# ImageSensor_IMX415.net
KiCad netlist of a schematic drawn in Altium Designer
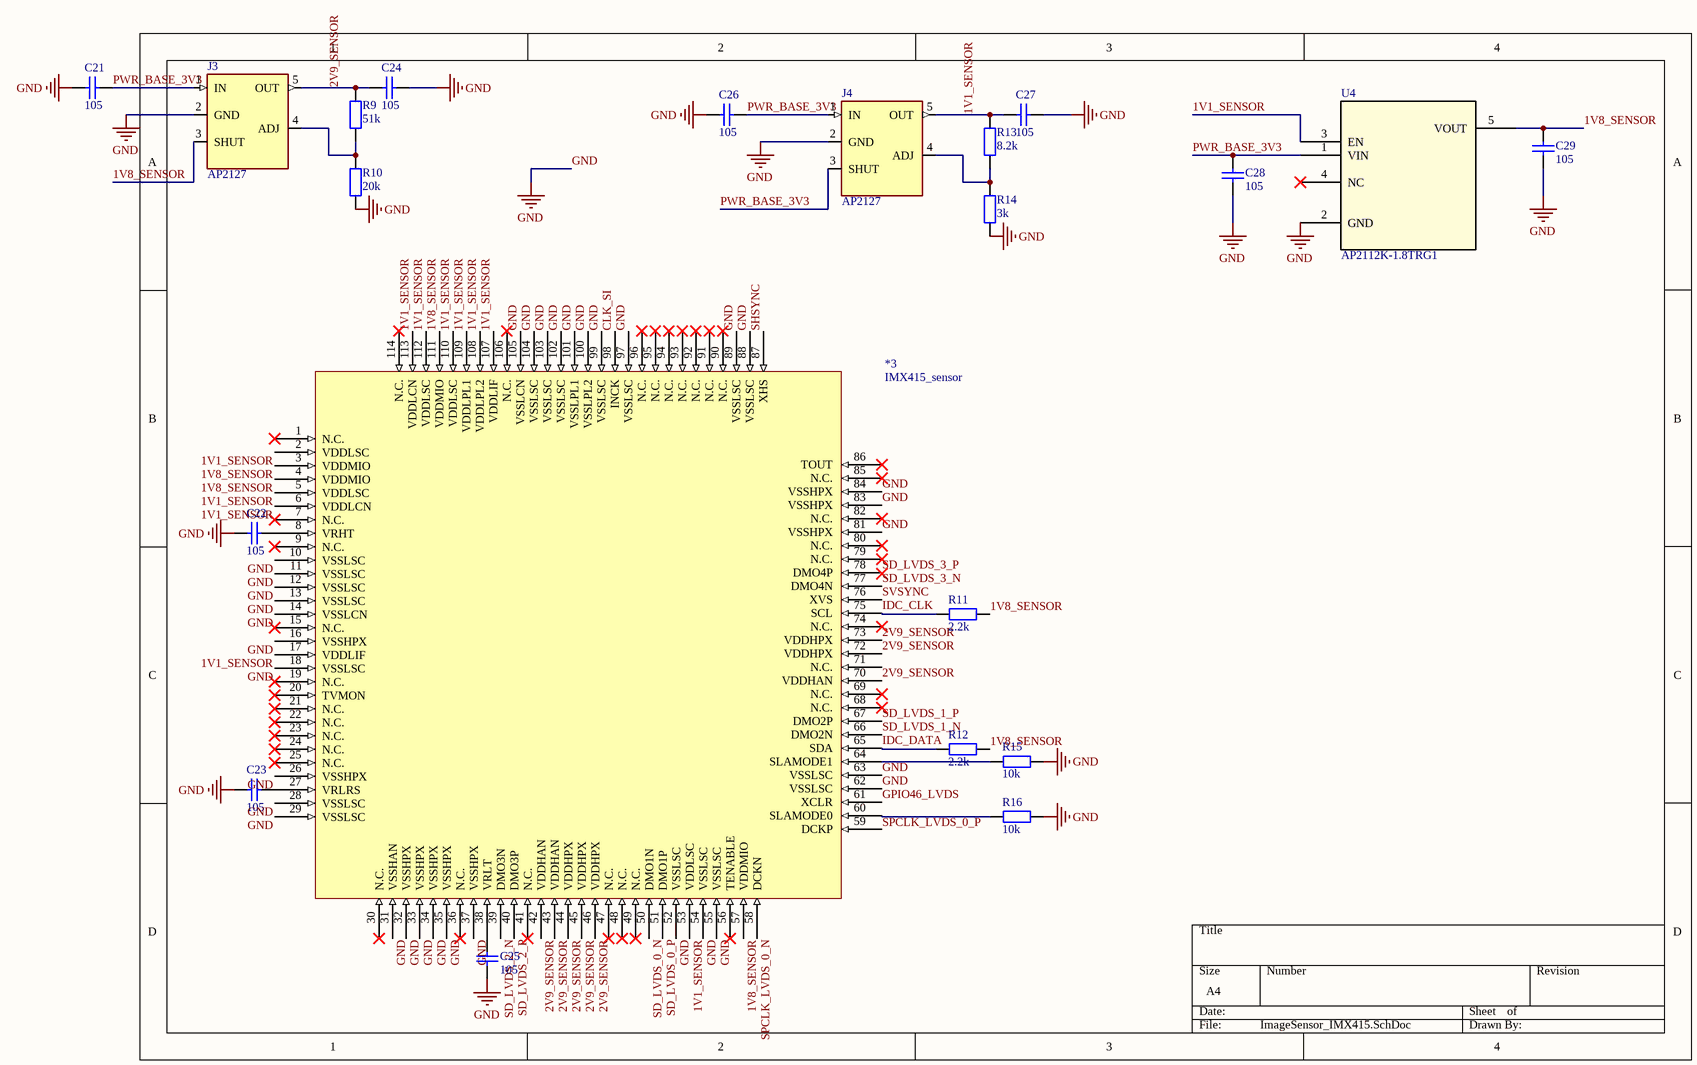
[diagram p0: ImageSensor_IMX415.SchDoc]

(export (version "E")
  (design (tool "Eeschema 10.0.6"))
  (components
    (comp (ref "*3")
      (value "IMX415_sensor")
      (footprint "IMX415_sensor - duplicate")
      (libsource (lib "MyLib") (part "IMX415_sensor"))
    )
    (comp (ref "C21")
      (value "105")
      (footprint "tu 0603")
      (description "Dán")
      (libsource (lib "Altium_Lib_by_KhueNguyenCreator") (part "Tu 0603 105 16V 20%"))
    )
    (comp (ref "C22")
      (value "105")
      (footprint "tu 0603")
      (description "Dán")
      (libsource (lib "Altium_Lib_by_KhueNguyenCreator") (part "Tu 0603 105 16V 20%"))
    )
    (comp (ref "C23")
      (value "105")
      (footprint "tu 0603")
      (description "Dán")
      (libsource (lib "Altium_Lib_by_KhueNguyenCreator") (part "Tu 0603 105 16V 20%"))
    )
    (comp (ref "C24")
      (value "105")
      (footprint "tu 0603")
      (description "Dán")
      (libsource (lib "Altium_Lib_by_KhueNguyenCreator") (part "Tu 0603 105 16V 20%"))
    )
    (comp (ref "C25")
      (value "105")
      (footprint "tu 0603")
      (description "Dán")
      (libsource (lib "Altium_Lib_by_KhueNguyenCreator") (part "Tu 0603 105 16V 20%"))
    )
    (comp (ref "C26")
      (value "105")
      (footprint "tu 0603")
      (description "Dán")
      (libsource (lib "Altium_Lib_by_KhueNguyenCreator") (part "Tu 0603 105 16V 20%"))
    )
    (comp (ref "C27")
      (value "105")
      (footprint "tu 0603")
      (description "Dán")
      (libsource (lib "Altium_Lib_by_KhueNguyenCreator") (part "Tu 0603 105 16V 20%"))
    )
    (comp (ref "C28")
      (value "105")
      (footprint "tu 0603")
      (description "Dán")
      (libsource (lib "Altium_Lib_by_KhueNguyenCreator") (part "Tu 0603 105 16V 20%"))
    )
    (comp (ref "C29")
      (value "105")
      (footprint "tu 0603")
      (description "Dán")
      (libsource (lib "Altium_Lib_by_KhueNguyenCreator") (part "Tu 0603 105 16V 20%"))
    )
    (comp (ref "J3")
      (value "AP2127")
      (footprint "AP2127K-3.3")
      (description "LDO Regulator Pos 1.8V 0.4A 5-Pin SOT-23 T/R / IC REG LDO 1.8V 0.3A SOT23-5")
      (fields (field (name "MF") "Diodes Incorporated"))
      (libsource (lib "AP2127") (part "AP2127"))
    )
    (comp (ref "J4")
      (value "AP2127")
      (footprint "AP2127K-3.3")
      (description "LDO Regulator Pos 1.8V 0.4A 5-Pin SOT-23 T/R / IC REG LDO 1.8V 0.3A SOT23-5")
      (fields (field (name "MF") "Diodes Incorporated"))
      (libsource (lib "AP2127") (part "AP2127"))
    )
    (comp (ref "R9")
      (value "51k")
      (footprint "tro smd 0603")
      (description "Dán")
      (libsource (lib "Altium_Lib_by_KhueNguyenCreator") (part "Tro 0603 5% 51k"))
    )
    (comp (ref "R10")
      (value "20k")
      (footprint "tro smd 0805")
      (description "Dán")
      (libsource (lib "Altium_Lib_by_KhueNguyenCreator") (part "Tro 0805 5% 20k"))
    )
    (comp (ref "R11")
      (value "2.2k")
      (footprint "tro smd 0805")
      (description "Dán")
      (libsource (lib "Altium_Lib_by_KhueNguyenCreator") (part "Tro 0805 5% 2.2k"))
    )
    (comp (ref "R12")
      (value "2.2k")
      (footprint "tro smd 0805")
      (description "Dán")
      (libsource (lib "Altium_Lib_by_KhueNguyenCreator") (part "Tro 0805 5% 2.2k"))
    )
    (comp (ref "R13")
      (value "8.2k")
      (footprint "tro smd 0805")
      (description "Dán")
      (libsource (lib "Altium_Lib_by_KhueNguyenCreator") (part "Tro 0805 5% 8.2k"))
    )
    (comp (ref "R14")
      (value "3k")
      (footprint "tro smd 0805")
      (description "Dán")
      (libsource (lib "Altium_Lib_by_KhueNguyenCreator") (part "Tro 0805 5% 3k"))
    )
    (comp (ref "R15")
      (value "10k")
      (footprint "tro smd 0603")
      (description "Dán")
      (libsource (lib "Altium_Lib_by_KhueNguyenCreator") (part "Tro 0603 1% 10k"))
    )
    (comp (ref "R16")
      (value "10k")
      (footprint "tro smd 0603")
      (description "Dán")
      (libsource (lib "Altium_Lib_by_KhueNguyenCreator") (part "Tro 0603 1% 10k"))
    )
    (comp (ref "U4")
      (value "AP2112K-1.8TRG1")
      (footprint "AP2112K-1.8TRG1_DIO")
      (description "Description")
      (fields (field (name "COPYRIGHT") "Copyright (C) 2026 Ultra Librarian. All rights reserved."))
      (libsource (lib "AP2112K-1P8TRG1") (part "AP2112K-1.8TRG1"))
    )
  )
  (nets
    (net (code "1") (name "/1V1_SENSOR") (class "Default")
      (node (ref "*3") (pin "107") (pinfunction "VDDLIF_107") (pintype "input"))
      (node (ref "*3") (pin "108") (pinfunction "VDDLPL2_108") (pintype "input"))
      (node (ref "*3") (pin "109") (pinfunction "VDDLPL1_109") (pintype "input"))
      (node (ref "*3") (pin "110") (pinfunction "VDDLSC_110") (pintype "input"))
      (node (ref "*3") (pin "112") (pinfunction "VDDLSC_112") (pintype "input"))
      (node (ref "*3") (pin "113") (pinfunction "VDDLCN_113") (pintype "input"))
      (node (ref "*3") (pin "17") (pinfunction "VDDLIF_17") (pintype "input"))
      (node (ref "*3") (pin "2") (pinfunction "VDDLSC_2") (pintype "input"))
      (node (ref "*3") (pin "5") (pinfunction "VDDLSC_5") (pintype "input"))
      (node (ref "*3") (pin "53") (pinfunction "VDDLSC_53") (pintype "input"))
      (node (ref "*3") (pin "6") (pinfunction "VDDLCN_6") (pintype "input"))
      (node (ref "C27") (pin "2") (pinfunction "2_2") (pintype "passive"))
      (node (ref "J4") (pin "5") (pinfunction "OUT_5") (pintype "output"))
      (node (ref "R13") (pin "2") (pinfunction "2_2") (pintype "passive"))
      (node (ref "U4") (pin "3") (pinfunction "EN_3") (pintype "passive"))
    )
    (net (code "2") (name "/1V8_SENSOR") (class "Default")
      (node (ref "*3") (pin "111") (pinfunction "VDDMIO_111") (pintype "input"))
      (node (ref "*3") (pin "3") (pinfunction "VDDMIO_3") (pintype "input"))
      (node (ref "*3") (pin "4") (pinfunction "VDDMIO_4") (pintype "input"))
      (node (ref "*3") (pin "57") (pinfunction "VDDMIO_57") (pintype "input"))
      (node (ref "C29") (pin "2") (pinfunction "2_2") (pintype "passive"))
      (node (ref "J3") (pin "3") (pinfunction "SHUT_3") (pintype "bidirectional"))
      (node (ref "R11") (pin "2") (pinfunction "2_2") (pintype "passive"))
      (node (ref "R12") (pin "2") (pinfunction "2_2") (pintype "passive"))
      (node (ref "U4") (pin "5") (pinfunction "VOUT_5") (pintype "passive"))
    )
    (net (code "3") (name "/2V9_SENSOR") (class "Default")
      (node (ref "*3") (pin "42") (pinfunction "VDDHAN_42") (pintype "input"))
      (node (ref "*3") (pin "43") (pinfunction "VDDHAN_43") (pintype "input"))
      (node (ref "*3") (pin "44") (pinfunction "VDDHPX_44") (pintype "input"))
      (node (ref "*3") (pin "45") (pinfunction "VDDHPX_45") (pintype "input"))
      (node (ref "*3") (pin "46") (pinfunction "VDDHPX_46") (pintype "input"))
      (node (ref "*3") (pin "70") (pinfunction "VDDHAN_70") (pintype "input"))
      (node (ref "*3") (pin "72") (pinfunction "VDDHPX_72") (pintype "input"))
      (node (ref "*3") (pin "73") (pinfunction "VDDHPX_73") (pintype "input"))
      (node (ref "C24") (pin "2") (pinfunction "2_2") (pintype "passive"))
      (node (ref "J3") (pin "5") (pinfunction "OUT_5") (pintype "output"))
      (node (ref "R9") (pin "2") (pinfunction "2_2") (pintype "passive"))
    )
    (net (code "4") (name "/CLK_SI") (class "Default")
      (node (ref "*3") (pin "98") (pinfunction "INCK_98") (pintype "input"))
    )
    (net (code "5") (name "/GPIO46_LVDS") (class "Default")
      (node (ref "*3") (pin "61") (pinfunction "XCLR_61") (pintype "input"))
    )
    (net (code "6") (name "/IDC_CLK") (class "Default")
      (node (ref "*3") (pin "75") (pinfunction "SCL_75") (pintype "input"))
      (node (ref "R11") (pin "1") (pinfunction "1_1") (pintype "passive"))
    )
    (net (code "7") (name "/IDC_DATA") (class "Default")
      (node (ref "*3") (pin "65") (pinfunction "SDA_65") (pintype "input"))
      (node (ref "R12") (pin "1") (pinfunction "1_1") (pintype "passive"))
    )
    (net (code "8") (name "/PWR_BASE_3V3") (class "Default")
      (node (ref "C21") (pin "2") (pinfunction "2_2") (pintype "passive"))
      (node (ref "C26") (pin "2") (pinfunction "2_2") (pintype "passive"))
      (node (ref "C28") (pin "2") (pinfunction "2_2") (pintype "passive"))
      (node (ref "J3") (pin "1") (pinfunction "IN_1") (pintype "input"))
      (node (ref "J4") (pin "1") (pinfunction "IN_1") (pintype "input"))
      (node (ref "J4") (pin "3") (pinfunction "SHUT_3") (pintype "bidirectional"))
      (node (ref "U4") (pin "1") (pinfunction "VIN_1") (pintype "passive"))
    )
    (net (code "9") (name "/SD_LVDS_0_N") (class "Default")
      (node (ref "*3") (pin "50") (pinfunction "DMO1N_50") (pintype "input"))
    )
    (net (code "10") (name "/SD_LVDS_0_P") (class "Default")
      (node (ref "*3") (pin "51") (pinfunction "DMO1P_51") (pintype "input"))
    )
    (net (code "11") (name "/SD_LVDS_1_N") (class "Default")
      (node (ref "*3") (pin "66") (pinfunction "DMO2N_66") (pintype "input"))
    )
    (net (code "12") (name "/SD_LVDS_1_P") (class "Default")
      (node (ref "*3") (pin "67") (pinfunction "DMO2P_67") (pintype "input"))
    )
    (net (code "13") (name "/SD_LVDS_2_N") (class "Default")
      (node (ref "*3") (pin "39") (pinfunction "DMO3N_39") (pintype "input"))
    )
    (net (code "14") (name "/SD_LVDS_2_P") (class "Default")
      (node (ref "*3") (pin "40") (pinfunction "DMO3P_40") (pintype "input"))
    )
    (net (code "15") (name "/SD_LVDS_3_N") (class "Default")
      (node (ref "*3") (pin "77") (pinfunction "DMO4N_77") (pintype "input"))
    )
    (net (code "16") (name "/SD_LVDS_3_P") (class "Default")
      (node (ref "*3") (pin "78") (pinfunction "DMO4P_78") (pintype "input"))
    )
    (net (code "17") (name "/SHSYNC") (class "Default")
      (node (ref "*3") (pin "87") (pinfunction "XHS_87") (pintype "input"))
    )
    (net (code "18") (name "/SPCLK_LVDS_0_N") (class "Default")
      (node (ref "*3") (pin "58") (pinfunction "DCKN_58") (pintype "input"))
    )
    (net (code "20") (name "/SVSYNC") (class "Default")
      (node (ref "*3") (pin "76") (pinfunction "XVS_76") (pintype "input"))
    )
    (net (code "21") (name "GND") (class "Default")
      (node (ref "*3") (pin "10") (pinfunction "VSSLSC_10") (pintype "input"))
      (node (ref "*3") (pin "100") (pinfunction "VSSLPL2_100") (pintype "input"))
      (node (ref "*3") (pin "101") (pinfunction "VSSLPL1_101") (pintype "input"))
      (node (ref "*3") (pin "102") (pinfunction "VSSLSC_102") (pintype "input"))
      (node (ref "*3") (pin "103") (pinfunction "VSSLSC_103") (pintype "input"))
      (node (ref "*3") (pin "104") (pinfunction "VSSLSC_104") (pintype "input"))
      (node (ref "*3") (pin "105") (pinfunction "VSSLCN_105") (pintype "input"))
      (node (ref "*3") (pin "11") (pinfunction "VSSLSC_11") (pintype "input"))
      (node (ref "*3") (pin "12") (pinfunction "VSSLSC_12") (pintype "input"))
      (node (ref "*3") (pin "13") (pinfunction "VSSLSC_13") (pintype "input"))
      (node (ref "*3") (pin "14") (pinfunction "VSSLCN_14") (pintype "input"))
      (node (ref "*3") (pin "16") (pinfunction "VSSHPX_16") (pintype "input"))
      (node (ref "*3") (pin "18") (pinfunction "VSSLSC_18") (pintype "input"))
      (node (ref "*3") (pin "26") (pinfunction "VSSHPX_26") (pintype "input"))
      (node (ref "*3") (pin "28") (pinfunction "VSSLSC_28") (pintype "input"))
      (node (ref "*3") (pin "29") (pinfunction "VSSLSC_29") (pintype "input"))
      (node (ref "*3") (pin "31") (pinfunction "VSSHAN_31") (pintype "input"))
      (node (ref "*3") (pin "32") (pinfunction "VSSHPX_32") (pintype "input"))
      (node (ref "*3") (pin "33") (pinfunction "VSSHPX_33") (pintype "input"))
      (node (ref "*3") (pin "34") (pinfunction "VSSHPX_34") (pintype "input"))
      (node (ref "*3") (pin "35") (pinfunction "VSSHPX_35") (pintype "input"))
      (node (ref "*3") (pin "37") (pinfunction "VSSHPX_37") (pintype "input"))
      (node (ref "*3") (pin "52") (pinfunction "VSSLSC_52") (pintype "input"))
      (node (ref "*3") (pin "54") (pinfunction "VSSLSC_54") (pintype "input"))
      (node (ref "*3") (pin "55") (pinfunction "VSSLSC_55") (pintype "input"))
      (node (ref "*3") (pin "62") (pinfunction "VSSLSC_62") (pintype "input"))
      (node (ref "*3") (pin "63") (pinfunction "VSSLSC_63") (pintype "input"))
      (node (ref "*3") (pin "81") (pinfunction "VSSHPX_81") (pintype "input"))
      (node (ref "*3") (pin "83") (pinfunction "VSSHPX_83") (pintype "input"))
      (node (ref "*3") (pin "84") (pinfunction "VSSHPX_84") (pintype "input"))
      (node (ref "*3") (pin "88") (pinfunction "VSSLSC_88") (pintype "input"))
      (node (ref "*3") (pin "89") (pinfunction "VSSLSC_89") (pintype "input"))
      (node (ref "*3") (pin "97") (pinfunction "VSSLSC_97") (pintype "input"))
      (node (ref "*3") (pin "99") (pinfunction "VSSLSC_99") (pintype "input"))
      (node (ref "C21") (pin "1") (pinfunction "1_1") (pintype "passive"))
      (node (ref "C22") (pin "2") (pinfunction "2_2") (pintype "passive"))
      (node (ref "C23") (pin "2") (pinfunction "2_2") (pintype "passive"))
      (node (ref "C24") (pin "1") (pinfunction "1_1") (pintype "passive"))
      (node (ref "C25") (pin "2") (pinfunction "2_2") (pintype "passive"))
      (node (ref "C26") (pin "1") (pinfunction "1_1") (pintype "passive"))
      (node (ref "C27") (pin "1") (pinfunction "1_1") (pintype "passive"))
      (node (ref "C28") (pin "1") (pinfunction "1_1") (pintype "passive"))
      (node (ref "C29") (pin "1") (pinfunction "1_1") (pintype "passive"))
      (node (ref "J3") (pin "2") (pinfunction "GND_2") (pintype "power_in"))
      (node (ref "J4") (pin "2") (pinfunction "GND_2") (pintype "power_in"))
      (node (ref "R10") (pin "1") (pinfunction "1_1") (pintype "passive"))
      (node (ref "R14") (pin "1") (pinfunction "1_1") (pintype "passive"))
      (node (ref "R15") (pin "1") (pinfunction "1_1") (pintype "passive"))
      (node (ref "R16") (pin "1") (pinfunction "1_1") (pintype "passive"))
      (node (ref "U4") (pin "2") (pinfunction "GND_2") (pintype "passive"))
    )
    (net (code "22") (name "Net-(*3-SLAMODE0)") (class "Default")
      (node (ref "*3") (pin "60") (pinfunction "SLAMODE0_60") (pintype "input"))
      (node (ref "R16") (pin "2") (pinfunction "2_2") (pintype "passive"))
    )
    (net (code "23") (name "Net-(*3-SLAMODE1)") (class "Default")
      (node (ref "*3") (pin "64") (pinfunction "SLAMODE1_64") (pintype "input"))
      (node (ref "R15") (pin "2") (pinfunction "2_2") (pintype "passive"))
    )
    (net (code "24") (name "Net-(*3-VRHT)") (class "Default")
      (node (ref "*3") (pin "8") (pinfunction "VRHT_8") (pintype "input"))
      (node (ref "C22") (pin "1") (pinfunction "1_1") (pintype "passive"))
    )
    (net (code "25") (name "Net-(*3-VRLRS)") (class "Default")
      (node (ref "*3") (pin "27") (pinfunction "VRLRS_27") (pintype "input"))
      (node (ref "C23") (pin "1") (pinfunction "1_1") (pintype "passive"))
    )
    (net (code "26") (name "Net-(*3-VRLT)") (class "Default")
      (node (ref "*3") (pin "38") (pinfunction "VRLT_38") (pintype "input"))
      (node (ref "C25") (pin "1") (pinfunction "1_1") (pintype "passive"))
    )
    (net (code "27") (name "Net-(J3-ADJ)") (class "Default")
      (node (ref "J3") (pin "4") (pinfunction "ADJ_4") (pintype "bidirectional"))
      (node (ref "R10") (pin "2") (pinfunction "2_2") (pintype "passive"))
      (node (ref "R9") (pin "1") (pinfunction "1_1") (pintype "passive"))
    )
    (net (code "28") (name "Net-(J4-ADJ)") (class "Default")
      (node (ref "J4") (pin "4") (pinfunction "ADJ_4") (pintype "bidirectional"))
      (node (ref "R13") (pin "1") (pinfunction "1_1") (pintype "passive"))
      (node (ref "R14") (pin "2") (pinfunction "2_2") (pintype "passive"))
    )
    (net (code "29") (name "unconnected-(*3-DCKP-Pad59)") (class "Default")
      (node (ref "*3") (pin "59") (pinfunction "DCKP_59") (pintype "input"))
    )
    (net (code "30") (name "unconnected-(*3-N.C.-Pad1)") (class "Default")
      (node (ref "*3") (pin "1") (pinfunction "N.C._1") (pintype "input+no_connect"))
    )
    (net (code "31") (name "unconnected-(*3-N.C.-Pad7)") (class "Default")
      (node (ref "*3") (pin "7") (pinfunction "N.C._7") (pintype "input+no_connect"))
    )
    (net (code "32") (name "unconnected-(*3-N.C.-Pad9)") (class "Default")
      (node (ref "*3") (pin "9") (pinfunction "N.C._9") (pintype "input+no_connect"))
    )
    (net (code "33") (name "unconnected-(*3-N.C.-Pad15)") (class "Default")
      (node (ref "*3") (pin "15") (pinfunction "N.C._15") (pintype "input+no_connect"))
    )
    (net (code "34") (name "unconnected-(*3-N.C.-Pad19)") (class "Default")
      (node (ref "*3") (pin "19") (pinfunction "N.C._19") (pintype "input+no_connect"))
    )
    (net (code "35") (name "unconnected-(*3-N.C.-Pad21)") (class "Default")
      (node (ref "*3") (pin "21") (pinfunction "N.C._21") (pintype "input+no_connect"))
    )
    (net (code "36") (name "unconnected-(*3-N.C.-Pad22)") (class "Default")
      (node (ref "*3") (pin "22") (pinfunction "N.C._22") (pintype "input+no_connect"))
    )
    (net (code "37") (name "unconnected-(*3-N.C.-Pad23)") (class "Default")
      (node (ref "*3") (pin "23") (pinfunction "N.C._23") (pintype "input+no_connect"))
    )
    (net (code "38") (name "unconnected-(*3-N.C.-Pad24)") (class "Default")
      (node (ref "*3") (pin "24") (pinfunction "N.C._24") (pintype "input+no_connect"))
    )
    (net (code "39") (name "unconnected-(*3-N.C.-Pad25)") (class "Default")
      (node (ref "*3") (pin "25") (pinfunction "N.C._25") (pintype "input+no_connect"))
    )
    (net (code "40") (name "unconnected-(*3-N.C.-Pad30)") (class "Default")
      (node (ref "*3") (pin "30") (pinfunction "N.C._30") (pintype "input+no_connect"))
    )
    (net (code "41") (name "unconnected-(*3-N.C.-Pad36)") (class "Default")
      (node (ref "*3") (pin "36") (pinfunction "N.C._36") (pintype "input+no_connect"))
    )
    (net (code "42") (name "unconnected-(*3-N.C.-Pad41)") (class "Default")
      (node (ref "*3") (pin "41") (pinfunction "N.C._41") (pintype "input+no_connect"))
    )
    (net (code "43") (name "unconnected-(*3-N.C.-Pad47)") (class "Default")
      (node (ref "*3") (pin "47") (pinfunction "N.C._47") (pintype "input+no_connect"))
    )
    (net (code "44") (name "unconnected-(*3-N.C.-Pad48)") (class "Default")
      (node (ref "*3") (pin "48") (pinfunction "N.C._48") (pintype "input+no_connect"))
    )
    (net (code "45") (name "unconnected-(*3-N.C.-Pad49)") (class "Default")
      (node (ref "*3") (pin "49") (pinfunction "N.C._49") (pintype "input+no_connect"))
    )
    (net (code "46") (name "unconnected-(*3-N.C.-Pad68)") (class "Default")
      (node (ref "*3") (pin "68") (pinfunction "N.C._68") (pintype "input+no_connect"))
    )
    (net (code "47") (name "unconnected-(*3-N.C.-Pad69)") (class "Default")
      (node (ref "*3") (pin "69") (pinfunction "N.C._69") (pintype "input+no_connect"))
    )
    (net (code "48") (name "unconnected-(*3-N.C.-Pad71)") (class "Default")
      (node (ref "*3") (pin "71") (pinfunction "N.C._71") (pintype "input"))
    )
    (net (code "49") (name "unconnected-(*3-N.C.-Pad74)") (class "Default")
      (node (ref "*3") (pin "74") (pinfunction "N.C._74") (pintype "input+no_connect"))
    )
    (net (code "50") (name "unconnected-(*3-N.C.-Pad79)") (class "Default")
      (node (ref "*3") (pin "79") (pinfunction "N.C._79") (pintype "input+no_connect"))
    )
    (net (code "51") (name "unconnected-(*3-N.C.-Pad80)") (class "Default")
      (node (ref "*3") (pin "80") (pinfunction "N.C._80") (pintype "input+no_connect"))
    )
    (net (code "52") (name "unconnected-(*3-N.C.-Pad82)") (class "Default")
      (node (ref "*3") (pin "82") (pinfunction "N.C._82") (pintype "input+no_connect"))
    )
    (net (code "53") (name "unconnected-(*3-N.C.-Pad85)") (class "Default")
      (node (ref "*3") (pin "85") (pinfunction "N.C._85") (pintype "input+no_connect"))
    )
    (net (code "54") (name "unconnected-(*3-N.C.-Pad90)") (class "Default")
      (node (ref "*3") (pin "90") (pinfunction "N.C._90") (pintype "input+no_connect"))
    )
    (net (code "55") (name "unconnected-(*3-N.C.-Pad91)") (class "Default")
      (node (ref "*3") (pin "91") (pinfunction "N.C._91") (pintype "input+no_connect"))
    )
    (net (code "56") (name "unconnected-(*3-N.C.-Pad92)") (class "Default")
      (node (ref "*3") (pin "92") (pinfunction "N.C._92") (pintype "input+no_connect"))
    )
    (net (code "57") (name "unconnected-(*3-N.C.-Pad93)") (class "Default")
      (node (ref "*3") (pin "93") (pinfunction "N.C._93") (pintype "input+no_connect"))
    )
    (net (code "58") (name "unconnected-(*3-N.C.-Pad94)") (class "Default")
      (node (ref "*3") (pin "94") (pinfunction "N.C._94") (pintype "input+no_connect"))
    )
    (net (code "59") (name "unconnected-(*3-N.C.-Pad95)") (class "Default")
      (node (ref "*3") (pin "95") (pinfunction "N.C._95") (pintype "input+no_connect"))
    )
    (net (code "60") (name "unconnected-(*3-N.C.-Pad96)") (class "Default")
      (node (ref "*3") (pin "96") (pinfunction "N.C._96") (pintype "input+no_connect"))
    )
    (net (code "61") (name "unconnected-(*3-N.C.-Pad106)") (class "Default")
      (node (ref "*3") (pin "106") (pinfunction "N.C._106") (pintype "input+no_connect"))
    )
    (net (code "62") (name "unconnected-(*3-N.C.-Pad114)") (class "Default")
      (node (ref "*3") (pin "114") (pinfunction "N.C._114") (pintype "input+no_connect"))
    )
    (net (code "63") (name "unconnected-(*3-TENABLE-Pad56)") (class "Default")
      (node (ref "*3") (pin "56") (pinfunction "TENABLE_56") (pintype "input+no_connect"))
    )
    (net (code "64") (name "unconnected-(*3-TOUT-Pad86)") (class "Default")
      (node (ref "*3") (pin "86") (pinfunction "TOUT_86") (pintype "input+no_connect"))
    )
    (net (code "65") (name "unconnected-(*3-TVMON-Pad20)") (class "Default")
      (node (ref "*3") (pin "20") (pinfunction "TVMON_20") (pintype "input+no_connect"))
    )
    (net (code "66") (name "unconnected-(U4-NC-Pad4)") (class "Default")
      (node (ref "U4") (pin "4") (pinfunction "NC_4") (pintype "passive+no_connect"))
    )
  )
)
